# 3_Power.net
KiCad netlist of a schematic drawn in Altium Designer
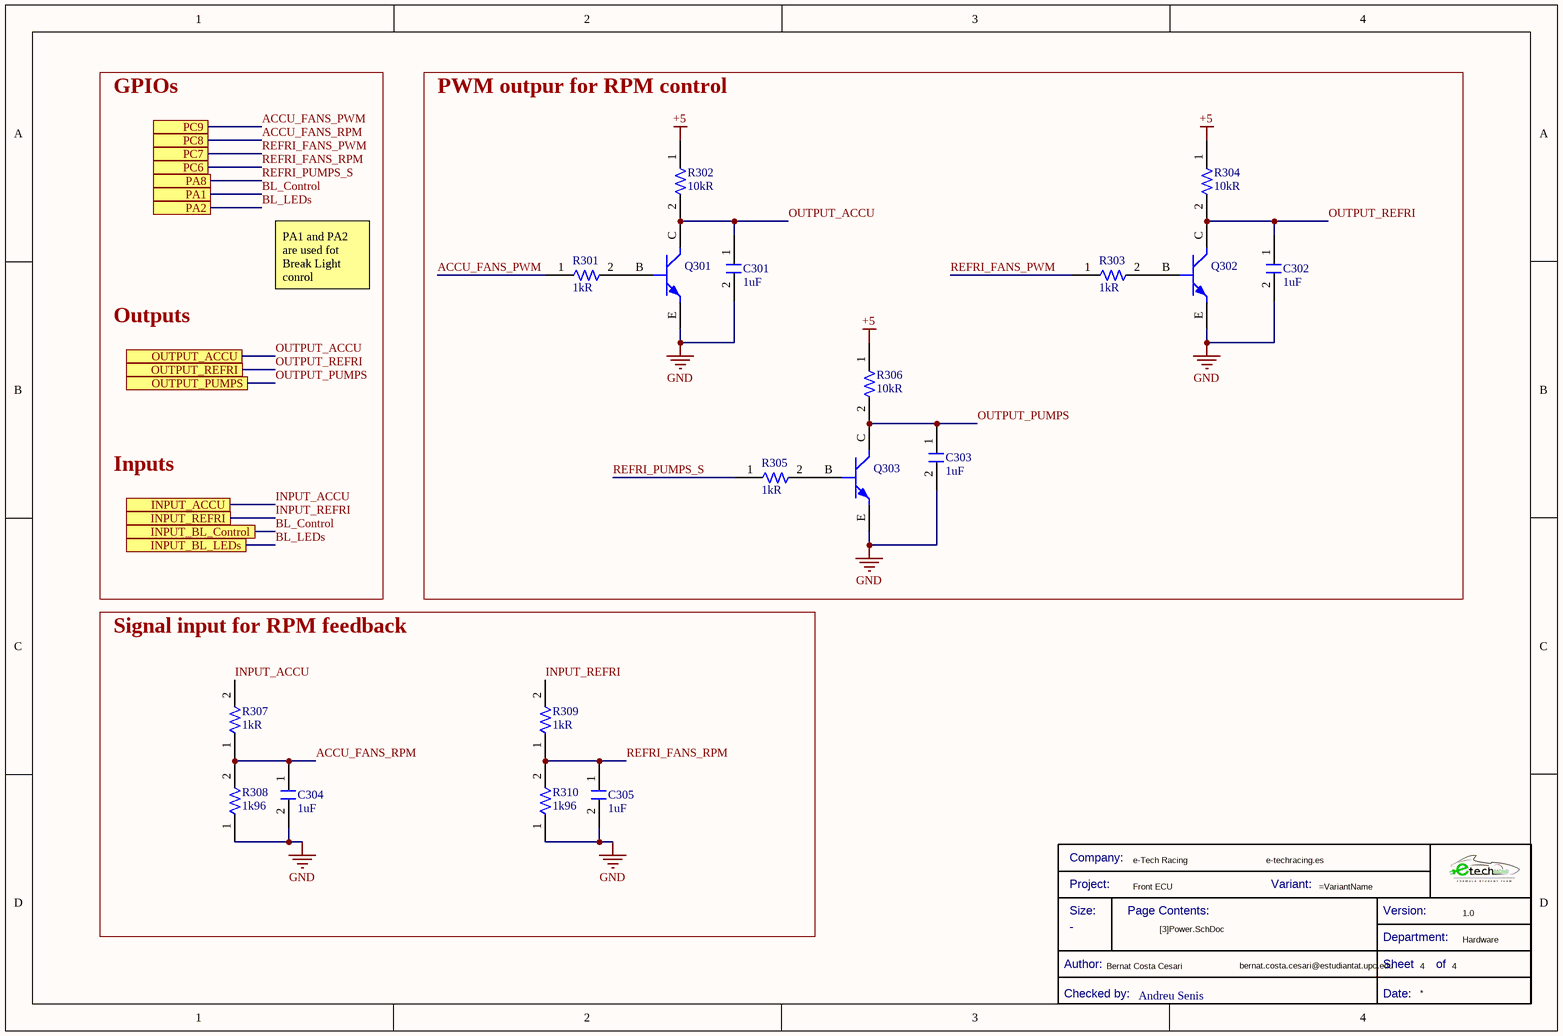
[diagram p0: [3]Power.SchDoc]

(export (version "E")
  (design (tool "Eeschema 10.0.6"))
  (components
    (comp (ref "C301")
      (value "885012207103")
      (footprint "C0805FNPC-R")
      (fields
        (field (name "TOLERANCE") "10%")
        (field (name "CAPACITANCE") "1uF")
        (field (name ".CREATOR") "GP")
      )
      (libsource (lib "Passives") (part "C1u-50V-0805FNPC-X7R"))
    )
    (comp (ref "C302")
      (value "885012207103")
      (footprint "C0805FNPC-R")
      (fields
        (field (name "TOLERANCE") "10%")
        (field (name "CAPACITANCE") "1uF")
        (field (name ".CREATOR") "GP")
      )
      (libsource (lib "Passives") (part "C1u-50V-0805FNPC-X7R"))
    )
    (comp (ref "C303")
      (value "885012207103")
      (footprint "C0805FNPC-R")
      (fields
        (field (name "TOLERANCE") "10%")
        (field (name "CAPACITANCE") "1uF")
        (field (name ".CREATOR") "GP")
      )
      (libsource (lib "Passives") (part "C1u-50V-0805FNPC-X7R"))
    )
    (comp (ref "C304")
      (value "885012207103")
      (footprint "C0805FNPC-R")
      (fields
        (field (name "TOLERANCE") "10%")
        (field (name "CAPACITANCE") "1uF")
        (field (name ".CREATOR") "GP")
      )
      (libsource (lib "Passives") (part "C1u-50V-0805FNPC-X7R"))
    )
    (comp (ref "C305")
      (value "885012207103")
      (footprint "C0805FNPC-R")
      (fields
        (field (name "TOLERANCE") "10%")
        (field (name "CAPACITANCE") "1uF")
        (field (name ".CREATOR") "GP")
      )
      (libsource (lib "Passives") (part "C1u-50V-0805FNPC-X7R"))
    )
    (comp (ref "Q301")
      (value "BC817-25LT1G")
      (footprint "TRT-NPN-0.5/45-SOT23")
      (description "ON Semi BC817-25LT1G NPN Bipolar Transistor; 0.5 A; 45 V; 3-Pin SOT-23")
      (fields (field (name ".CREATOR") "GP"))
      (libsource (lib "Semiconductor") (part "TRT-NPN-0.5/45-SOT23"))
    )
    (comp (ref "Q302")
      (value "BC817-25LT1G")
      (footprint "TRT-NPN-0.5/45-SOT23")
      (description "ON Semi BC817-25LT1G NPN Bipolar Transistor; 0.5 A; 45 V; 3-Pin SOT-23")
      (fields (field (name ".CREATOR") "GP"))
      (libsource (lib "Semiconductor") (part "TRT-NPN-0.5/45-SOT23"))
    )
    (comp (ref "Q303")
      (value "BC817-25LT1G")
      (footprint "TRT-NPN-0.5/45-SOT23")
      (description "ON Semi BC817-25LT1G NPN Bipolar Transistor; 0.5 A; 45 V; 3-Pin SOT-23")
      (fields (field (name ".CREATOR") "GP"))
      (libsource (lib "Semiconductor") (part "TRT-NPN-0.5/45-SOT23"))
    )
    (comp (ref "R301")
      (value "CR0805-JW-102ELF")
      (footprint "R0805FTK")
      (description "Res Thick Film 0805 1K Ohm 5% 1/8W ±200ppm/°C Molded SMD SMD Paper Tape on Plastic Reel")
      (fields
        (field (name "TOLERANCE") "5%")
        (field (name "RESISTANCE") "1kR")
        (field (name ".CREATOR") "GP")
      )
      (libsource (lib "Passives") (part "R1k-0805FTK"))
    )
    (comp (ref "R302")
      (value "CR0805-JW-103ELF")
      (footprint "R0805FTK")
      (fields
        (field (name "TOLERANCE") "5%")
        (field (name "RESISTANCE") "10kR")
        (field (name ".CREATOR") "DR")
      )
      (libsource (lib "Passives") (part "R10k-0805FTK"))
    )
    (comp (ref "R303")
      (value "CR0805-JW-102ELF")
      (footprint "R0805FTK")
      (description "Res Thick Film 0805 1K Ohm 5% 1/8W ±200ppm/°C Molded SMD SMD Paper Tape on Plastic Reel")
      (fields
        (field (name "TOLERANCE") "5%")
        (field (name "RESISTANCE") "1kR")
        (field (name ".CREATOR") "GP")
      )
      (libsource (lib "Passives") (part "R1k-0805FTK"))
    )
    (comp (ref "R304")
      (value "CR0805-JW-103ELF")
      (footprint "R0805FTK")
      (fields
        (field (name "TOLERANCE") "5%")
        (field (name "RESISTANCE") "10kR")
        (field (name ".CREATOR") "DR")
      )
      (libsource (lib "Passives") (part "R10k-0805FTK"))
    )
    (comp (ref "R305")
      (value "CR0805-JW-102ELF")
      (footprint "R0805FTK")
      (description "Res Thick Film 0805 1K Ohm 5% 1/8W ±200ppm/°C Molded SMD SMD Paper Tape on Plastic Reel")
      (fields
        (field (name "TOLERANCE") "5%")
        (field (name "RESISTANCE") "1kR")
        (field (name ".CREATOR") "GP")
      )
      (libsource (lib "Passives") (part "R1k-0805FTK"))
    )
    (comp (ref "R306")
      (value "CR0805-JW-103ELF")
      (footprint "R0805FTK")
      (fields
        (field (name "TOLERANCE") "5%")
        (field (name "RESISTANCE") "10kR")
        (field (name ".CREATOR") "DR")
      )
      (libsource (lib "Passives") (part "R10k-0805FTK"))
    )
    (comp (ref "R307")
      (value "CR0805-JW-102ELF")
      (footprint "R0805FTK")
      (description "Res Thick Film 0805 1K Ohm 5% 1/8W ±200ppm/°C Molded SMD SMD Paper Tape on Plastic Reel")
      (fields
        (field (name "TOLERANCE") "5%")
        (field (name "RESISTANCE") "1kR")
        (field (name ".CREATOR") "GP")
      )
      (libsource (lib "Passives") (part "R1k-0805FTK"))
    )
    (comp (ref "R308")
      (value "1k96")
      (footprint "R0805FTK")
      (libsource (lib "Passives") (part "R1k96-0805FTK"))
    )
    (comp (ref "R309")
      (value "CR0805-JW-102ELF")
      (footprint "R0805FTK")
      (description "Res Thick Film 0805 1K Ohm 5% 1/8W ±200ppm/°C Molded SMD SMD Paper Tape on Plastic Reel")
      (fields
        (field (name "TOLERANCE") "5%")
        (field (name "RESISTANCE") "1kR")
        (field (name ".CREATOR") "GP")
      )
      (libsource (lib "Passives") (part "R1k-0805FTK"))
    )
    (comp (ref "R310")
      (value "1k96")
      (footprint "R0805FTK")
      (libsource (lib "Passives") (part "R1k96-0805FTK"))
    )
  )
  (nets
    (net (code "1") (name "+5") (class "Default")
      (node (ref "R302") (pin "1") (pinfunction "1_1") (pintype "passive"))
      (node (ref "R304") (pin "1") (pinfunction "1_1") (pintype "passive"))
      (node (ref "R306") (pin "1") (pinfunction "1_1") (pintype "passive"))
    )
    (net (code "2") (name "/ACCU_FANS_PWM") (class "Default")
      (node (ref "R301") (pin "1") (pinfunction "1_1") (pintype "passive"))
    )
    (net (code "3") (name "/ACCU_FANS_RPM") (class "Default")
      (node (ref "C304") (pin "1") (pinfunction "1_1") (pintype "passive"))
      (node (ref "R307") (pin "1") (pinfunction "1_1") (pintype "passive"))
      (node (ref "R308") (pin "2") (pinfunction "2_2") (pintype "passive"))
    )
    (net (code "6") (name "/INPUT_ACCU") (class "Default")
      (node (ref "R307") (pin "2") (pinfunction "2_2") (pintype "passive"))
    )
    (net (code "7") (name "/INPUT_REFRI") (class "Default")
      (node (ref "R309") (pin "2") (pinfunction "2_2") (pintype "passive"))
    )
    (net (code "8") (name "/OUTPUT_ACCU") (class "Default")
      (node (ref "C301") (pin "1") (pinfunction "1_1") (pintype "passive"))
      (node (ref "Q301") (pin "C") (pinfunction "C_C") (pintype "passive"))
      (node (ref "R302") (pin "2") (pinfunction "2_2") (pintype "passive"))
    )
    (net (code "9") (name "/OUTPUT_PUMPS") (class "Default")
      (node (ref "C303") (pin "1") (pinfunction "1_1") (pintype "passive"))
      (node (ref "Q303") (pin "C") (pinfunction "C_C") (pintype "passive"))
      (node (ref "R306") (pin "2") (pinfunction "2_2") (pintype "passive"))
    )
    (net (code "10") (name "/OUTPUT_REFRI") (class "Default")
      (node (ref "C302") (pin "1") (pinfunction "1_1") (pintype "passive"))
      (node (ref "Q302") (pin "C") (pinfunction "C_C") (pintype "passive"))
      (node (ref "R304") (pin "2") (pinfunction "2_2") (pintype "passive"))
    )
    (net (code "11") (name "/REFRI_FANS_PWM") (class "Default")
      (node (ref "R303") (pin "1") (pinfunction "1_1") (pintype "passive"))
    )
    (net (code "12") (name "/REFRI_FANS_RPM") (class "Default")
      (node (ref "C305") (pin "1") (pinfunction "1_1") (pintype "passive"))
      (node (ref "R309") (pin "1") (pinfunction "1_1") (pintype "passive"))
      (node (ref "R310") (pin "2") (pinfunction "2_2") (pintype "passive"))
    )
    (net (code "13") (name "/REFRI_PUMPS_S") (class "Default")
      (node (ref "R305") (pin "1") (pinfunction "1_1") (pintype "passive"))
    )
    (net (code "14") (name "GND") (class "Default")
      (node (ref "C301") (pin "2") (pinfunction "2_2") (pintype "passive"))
      (node (ref "C302") (pin "2") (pinfunction "2_2") (pintype "passive"))
      (node (ref "C303") (pin "2") (pinfunction "2_2") (pintype "passive"))
      (node (ref "C304") (pin "2") (pinfunction "2_2") (pintype "passive"))
      (node (ref "C305") (pin "2") (pinfunction "2_2") (pintype "passive"))
      (node (ref "Q301") (pin "E") (pinfunction "E_E") (pintype "passive"))
      (node (ref "Q302") (pin "E") (pinfunction "E_E") (pintype "passive"))
      (node (ref "Q303") (pin "E") (pinfunction "E_E") (pintype "passive"))
      (node (ref "R308") (pin "1") (pinfunction "1_1") (pintype "passive"))
      (node (ref "R310") (pin "1") (pinfunction "1_1") (pintype "passive"))
    )
    (net (code "15") (name "Net-(Q301-PadB)") (class "Default")
      (node (ref "Q301") (pin "B") (pinfunction "B_B") (pintype "passive"))
      (node (ref "R301") (pin "2") (pinfunction "2_2") (pintype "passive"))
    )
    (net (code "16") (name "Net-(Q302-PadB)") (class "Default")
      (node (ref "Q302") (pin "B") (pinfunction "B_B") (pintype "passive"))
      (node (ref "R303") (pin "2") (pinfunction "2_2") (pintype "passive"))
    )
    (net (code "17") (name "Net-(Q303-PadB)") (class "Default")
      (node (ref "Q303") (pin "B") (pinfunction "B_B") (pintype "passive"))
      (node (ref "R305") (pin "2") (pinfunction "2_2") (pintype "passive"))
    )
  )
)
